# GPS_LoraWAN.net
KiCad netlist of a schematic drawn in Altium Designer
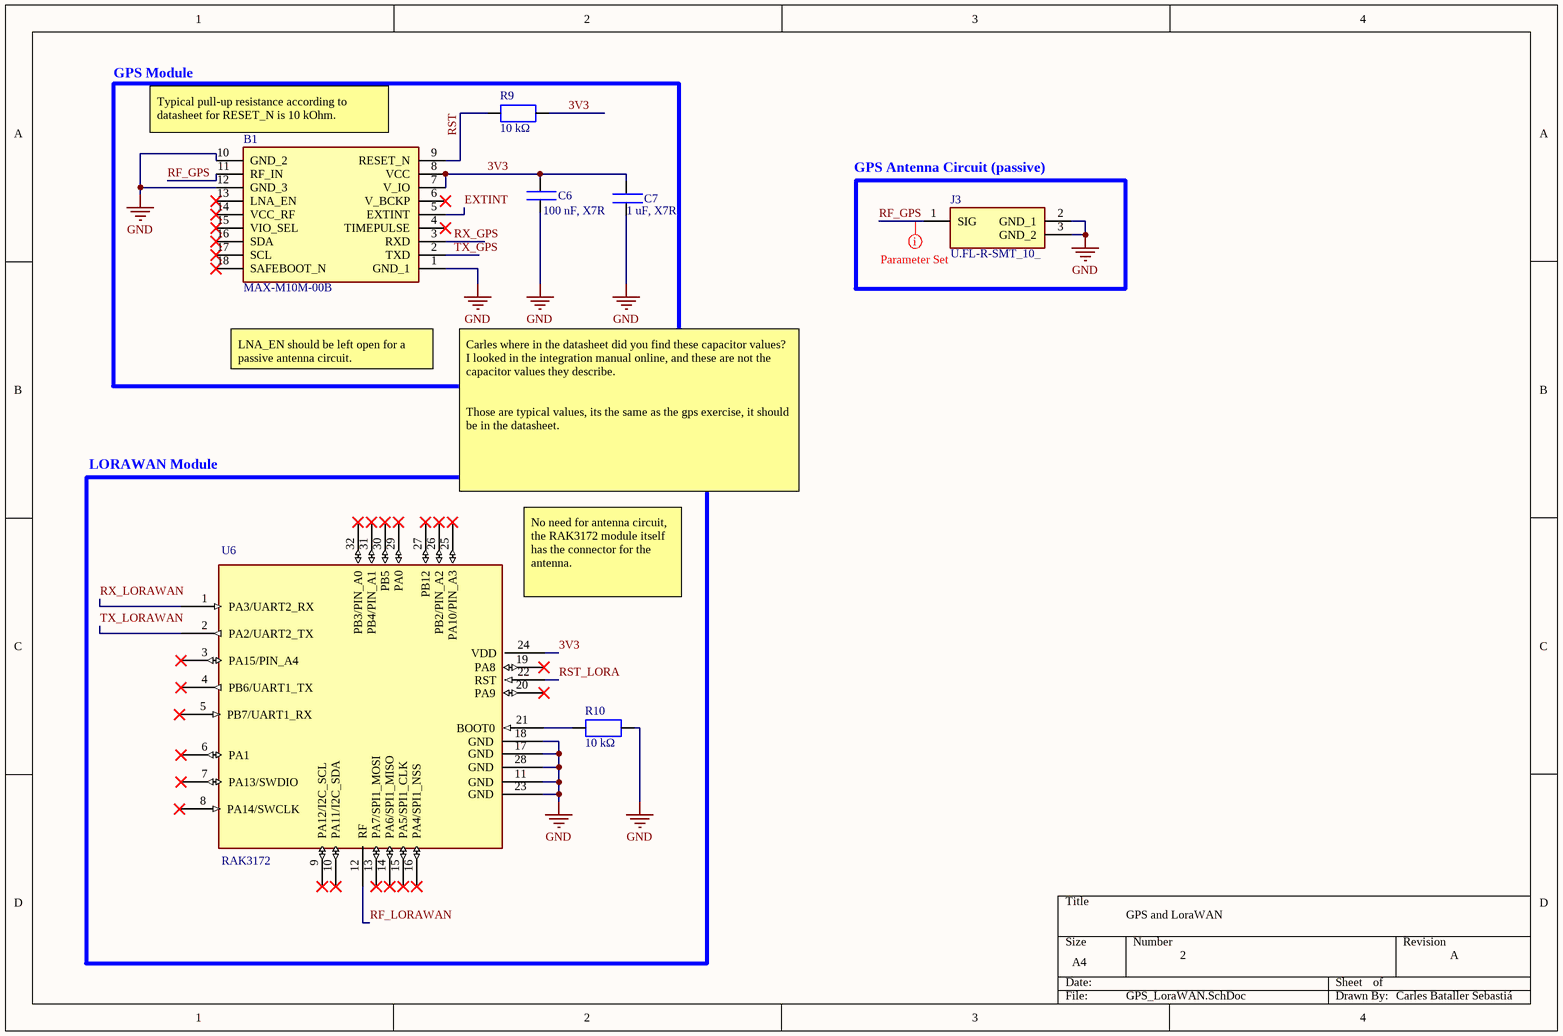
[diagram p0: GPS_LoraWAN.SchDoc]

(export (version "E")
  (design (tool "Eeschema 10.0.6"))
  (components
    (comp (ref "B1")
      (value "MAX-M10M-00B")
      (footprint "MAXM10M00B")
      (description "GPS Modules u-blox M10 GNSS LCC module, firmware in ROM, crystal oscillator")
      (fields (field (name "MOUSER PART NUMBER") "377-MAX-M10M-00B"))
      (libsource (lib "Generic-Schematic-Library") (part "MAX-M10M-00B"))
    )
    (comp (ref "C6")
      (value "100 nF, X7R")
      (footprint "CAP_0402")
      (description "Multilayer Ceramic Capacitors MLCC - SMD/SMT CAP")
      (fields (field (name "LCSC PART NUMBER") "C106200") (field (name "TOLERANCE") "5%"))
      (libsource (lib "Generic-Schematic-Library") (part "CAP_0402"))
    )
    (comp (ref "C7")
      (value "1 uF, X7R")
      (footprint "CAP_0402")
      (description "Multilayer Ceramic Capacitors MLCC - SMD/SMT 6.3V 1uF X7R 0402 10% HI CV")
      (fields (field (name "LCSC PART NUMBER") "C106200") (field (name "TOLERANCE") "5%"))
      (libsource (lib "Generic-Schematic-Library") (part "CAP_0402"))
    )
    (comp (ref "J3")
      (value "U.FL-R-SMT_10_")
      (footprint "UFLRSMT10")
      (description "U.FL (UMCC) Connector Receptacle, Male Pin 50 Ohms Surface Mount Solder")
      (fields (field (name "ARROW PART NUMBER") "U.FL-R-SMT(10)"))
      (libsource (lib "Generic-Schematic-Library") (part "U.FL-R-SMT_10_"))
    )
    (comp (ref "R9")
      (value "10 kΩ")
      (footprint "RES_0402")
      (description "Resistor SMD 0402 Generic")
      (fields (field (name "TOLERANCE") "1%") (field (name "LCSC PART NUMBER") "C93947"))
      (libsource (lib "Generic-Schematic-Library") (part "RES_0402"))
    )
    (comp (ref "R10")
      (value "10 kΩ")
      (footprint "RES_0201")
      (description "Thick Film Resistors - SMD 0201 10K0 1% Lead Free")
      (fields (field (name "TOLERANCE") "0.1%") (field (name "LCSC PART NUMBER") "C852221"))
      (libsource (lib "Generic-Schematic-Library") (part "RES_0201"))
    )
    (comp (ref "U6")
      (value "RAK3172")
      (footprint "XCVR_RAK3172")
      (description "Low-power, long-range transceiver module based on the STM32WLE5CC")
      (libsource (lib "Generic-Schematic-Library") (part "RAK3172"))
    )
  )
  (nets
    (net (code "1") (name "/3V3") (class "Default")
      (node (ref "B1") (pin "7") (pinfunction "V_IO_7") (pintype "passive"))
      (node (ref "B1") (pin "8") (pinfunction "VCC_8") (pintype "passive"))
      (node (ref "C6") (pin "2") (pinfunction "2_2") (pintype "passive"))
      (node (ref "C7") (pin "2") (pinfunction "2_2") (pintype "passive"))
      (node (ref "R9") (pin "2") (pinfunction "2_2") (pintype "passive"))
      (node (ref "U6") (pin "24") (pinfunction "VDD_24") (pintype "power_in"))
    )
    (net (code "2") (name "/EXTINT") (class "Default")
      (node (ref "B1") (pin "5") (pinfunction "EXTINT_5") (pintype "passive"))
    )
    (net (code "3") (name "/RF_GPS") (class "Default")
      (node (ref "B1") (pin "11") (pinfunction "RF_IN_11") (pintype "passive"))
      (node (ref "J3") (pin "1") (pinfunction "SIG_1") (pintype "passive"))
    )
    (net (code "4") (name "/RF_LORAWAN") (class "Default")
      (node (ref "U6") (pin "12") (pinfunction "RF_12") (pintype "passive"))
    )
    (net (code "5") (name "/RST") (class "Default")
      (node (ref "B1") (pin "9") (pinfunction "RESET_N_9") (pintype "passive"))
      (node (ref "R9") (pin "1") (pinfunction "1_1") (pintype "passive"))
    )
    (net (code "6") (name "/RST_LORA") (class "Default")
      (node (ref "U6") (pin "22") (pinfunction "RST_22") (pintype "input"))
    )
    (net (code "7") (name "/RX_GPS") (class "Default")
      (node (ref "B1") (pin "3") (pinfunction "RXD_3") (pintype "passive"))
    )
    (net (code "8") (name "/RX_LORAWAN") (class "Default")
      (node (ref "U6") (pin "1") (pinfunction "PA3/UART2_RX_1") (pintype "input"))
    )
    (net (code "9") (name "/TX_GPS") (class "Default")
      (node (ref "B1") (pin "2") (pinfunction "TXD_2") (pintype "passive"))
    )
    (net (code "10") (name "/TX_LORAWAN") (class "Default")
      (node (ref "U6") (pin "2") (pinfunction "PA2/UART2_TX_2") (pintype "output"))
    )
    (net (code "11") (name "GND") (class "Default")
      (node (ref "B1") (pin "1") (pinfunction "GND_1_1") (pintype "passive"))
      (node (ref "B1") (pin "10") (pinfunction "GND_2_10") (pintype "passive"))
      (node (ref "B1") (pin "12") (pinfunction "GND_3_12") (pintype "passive"))
      (node (ref "C6") (pin "1") (pinfunction "1_1") (pintype "passive"))
      (node (ref "C7") (pin "1") (pinfunction "1_1") (pintype "passive"))
      (node (ref "J3") (pin "2") (pinfunction "GND_1_2") (pintype "passive"))
      (node (ref "J3") (pin "3") (pinfunction "GND_2_3") (pintype "passive"))
      (node (ref "R10") (pin "2") (pinfunction "2_2") (pintype "passive"))
      (node (ref "U6") (pin "11") (pinfunction "GND_11") (pintype "power_in"))
      (node (ref "U6") (pin "17") (pinfunction "GND_17") (pintype "power_in"))
      (node (ref "U6") (pin "18") (pinfunction "GND_18") (pintype "power_in"))
      (node (ref "U6") (pin "23") (pinfunction "GND_23") (pintype "power_in"))
      (node (ref "U6") (pin "28") (pinfunction "GND_28") (pintype "power_in"))
    )
    (net (code "12") (name "Net-(U6-BOOT0)") (class "Default")
      (node (ref "R10") (pin "1") (pinfunction "1_1") (pintype "passive"))
      (node (ref "U6") (pin "21") (pinfunction "BOOT0_21") (pintype "input"))
    )
    (net (code "13") (name "unconnected-(B1-LNA_EN-Pad13)") (class "Default")
      (node (ref "B1") (pin "13") (pinfunction "LNA_EN_13") (pintype "passive+no_connect"))
    )
    (net (code "14") (name "unconnected-(B1-SAFEBOOT_N-Pad18)") (class "Default")
      (node (ref "B1") (pin "18") (pinfunction "SAFEBOOT_N_18") (pintype "passive+no_connect"))
    )
    (net (code "15") (name "unconnected-(B1-SCL-Pad17)") (class "Default")
      (node (ref "B1") (pin "17") (pinfunction "SCL_17") (pintype "passive+no_connect"))
    )
    (net (code "16") (name "unconnected-(B1-SDA-Pad16)") (class "Default")
      (node (ref "B1") (pin "16") (pinfunction "SDA_16") (pintype "passive+no_connect"))
    )
    (net (code "17") (name "unconnected-(B1-TIMEPULSE-Pad4)") (class "Default")
      (node (ref "B1") (pin "4") (pinfunction "TIMEPULSE_4") (pintype "passive+no_connect"))
    )
    (net (code "18") (name "unconnected-(B1-VCC_RF-Pad14)") (class "Default")
      (node (ref "B1") (pin "14") (pinfunction "VCC_RF_14") (pintype "passive+no_connect"))
    )
    (net (code "19") (name "unconnected-(B1-VIO_SEL-Pad15)") (class "Default")
      (node (ref "B1") (pin "15") (pinfunction "VIO_SEL_15") (pintype "passive+no_connect"))
    )
    (net (code "20") (name "unconnected-(B1-V_BCKP-Pad6)") (class "Default")
      (node (ref "B1") (pin "6") (pinfunction "V_BCKP_6") (pintype "passive+no_connect"))
    )
    (net (code "21") (name "unconnected-(U6-PA0-Pad29)") (class "Default")
      (node (ref "U6") (pin "29") (pinfunction "PA0_29") (pintype "bidirectional+no_connect"))
    )
    (net (code "22") (name "unconnected-(U6-PA1-Pad6)") (class "Default")
      (node (ref "U6") (pin "6") (pinfunction "PA1_6") (pintype "bidirectional+no_connect"))
    )
    (net (code "23") (name "unconnected-(U6-PA4{slash}SPI1_NSS-Pad16)") (class "Default")
      (node (ref "U6") (pin "16") (pinfunction "PA4/SPI1_NSS_16") (pintype "bidirectional+no_connect"))
    )
    (net (code "24") (name "unconnected-(U6-PA5{slash}SPI1_CLK-Pad15)") (class "Default")
      (node (ref "U6") (pin "15") (pinfunction "PA5/SPI1_CLK_15") (pintype "bidirectional+no_connect"))
    )
    (net (code "25") (name "unconnected-(U6-PA6{slash}SPI1_MISO-Pad14)") (class "Default")
      (node (ref "U6") (pin "14") (pinfunction "PA6/SPI1_MISO_14") (pintype "bidirectional+no_connect"))
    )
    (net (code "26") (name "unconnected-(U6-PA7{slash}SPI1_MOSI-Pad13)") (class "Default")
      (node (ref "U6") (pin "13") (pinfunction "PA7/SPI1_MOSI_13") (pintype "bidirectional+no_connect"))
    )
    (net (code "27") (name "unconnected-(U6-PA8-Pad19)") (class "Default")
      (node (ref "U6") (pin "19") (pinfunction "PA8_19") (pintype "bidirectional+no_connect"))
    )
    (net (code "28") (name "unconnected-(U6-PA9-Pad20)") (class "Default")
      (node (ref "U6") (pin "20") (pinfunction "PA9_20") (pintype "bidirectional+no_connect"))
    )
    (net (code "29") (name "unconnected-(U6-PA10{slash}PIN_A3-Pad25)") (class "Default")
      (node (ref "U6") (pin "25") (pinfunction "PA10/PIN_A3_25") (pintype "bidirectional+no_connect"))
    )
    (net (code "30") (name "unconnected-(U6-PA11{slash}I2C_SDA-Pad10)") (class "Default")
      (node (ref "U6") (pin "10") (pinfunction "PA11/I2C_SDA_10") (pintype "bidirectional+no_connect"))
    )
    (net (code "31") (name "unconnected-(U6-PA12{slash}I2C_SCL-Pad9)") (class "Default")
      (node (ref "U6") (pin "9") (pinfunction "PA12/I2C_SCL_9") (pintype "bidirectional+no_connect"))
    )
    (net (code "32") (name "unconnected-(U6-PA13{slash}SWDIO-Pad7)") (class "Default")
      (node (ref "U6") (pin "7") (pinfunction "PA13/SWDIO_7") (pintype "bidirectional+no_connect"))
    )
    (net (code "33") (name "unconnected-(U6-PA14{slash}SWCLK-Pad8)") (class "Default")
      (node (ref "U6") (pin "8") (pinfunction "PA14/SWCLK_8") (pintype "input+no_connect"))
    )
    (net (code "34") (name "unconnected-(U6-PA15{slash}PIN_A4-Pad3)") (class "Default")
      (node (ref "U6") (pin "3") (pinfunction "PA15/PIN_A4_3") (pintype "bidirectional+no_connect"))
    )
    (net (code "35") (name "unconnected-(U6-PB2{slash}PIN_A2-Pad26)") (class "Default")
      (node (ref "U6") (pin "26") (pinfunction "PB2/PIN_A2_26") (pintype "bidirectional+no_connect"))
    )
    (net (code "36") (name "unconnected-(U6-PB3{slash}PIN_A0-Pad32)") (class "Default")
      (node (ref "U6") (pin "32") (pinfunction "PB3/PIN_A0_32") (pintype "bidirectional+no_connect"))
    )
    (net (code "37") (name "unconnected-(U6-PB4{slash}PIN_A1-Pad31)") (class "Default")
      (node (ref "U6") (pin "31") (pinfunction "PB4/PIN_A1_31") (pintype "bidirectional+no_connect"))
    )
    (net (code "38") (name "unconnected-(U6-PB5-Pad30)") (class "Default")
      (node (ref "U6") (pin "30") (pinfunction "PB5_30") (pintype "bidirectional+no_connect"))
    )
    (net (code "39") (name "unconnected-(U6-PB6{slash}UART1_TX-Pad4)") (class "Default")
      (node (ref "U6") (pin "4") (pinfunction "PB6/UART1_TX_4") (pintype "output+no_connect"))
    )
    (net (code "40") (name "unconnected-(U6-PB7{slash}UART1_RX-Pad5)") (class "Default")
      (node (ref "U6") (pin "5") (pinfunction "PB7/UART1_RX_5") (pintype "input+no_connect"))
    )
    (net (code "41") (name "unconnected-(U6-PB12-Pad27)") (class "Default")
      (node (ref "U6") (pin "27") (pinfunction "PB12_27") (pintype "bidirectional+no_connect"))
    )
  )
)
